# ENET.net
KiCad netlist of a schematic drawn in Altium Designer
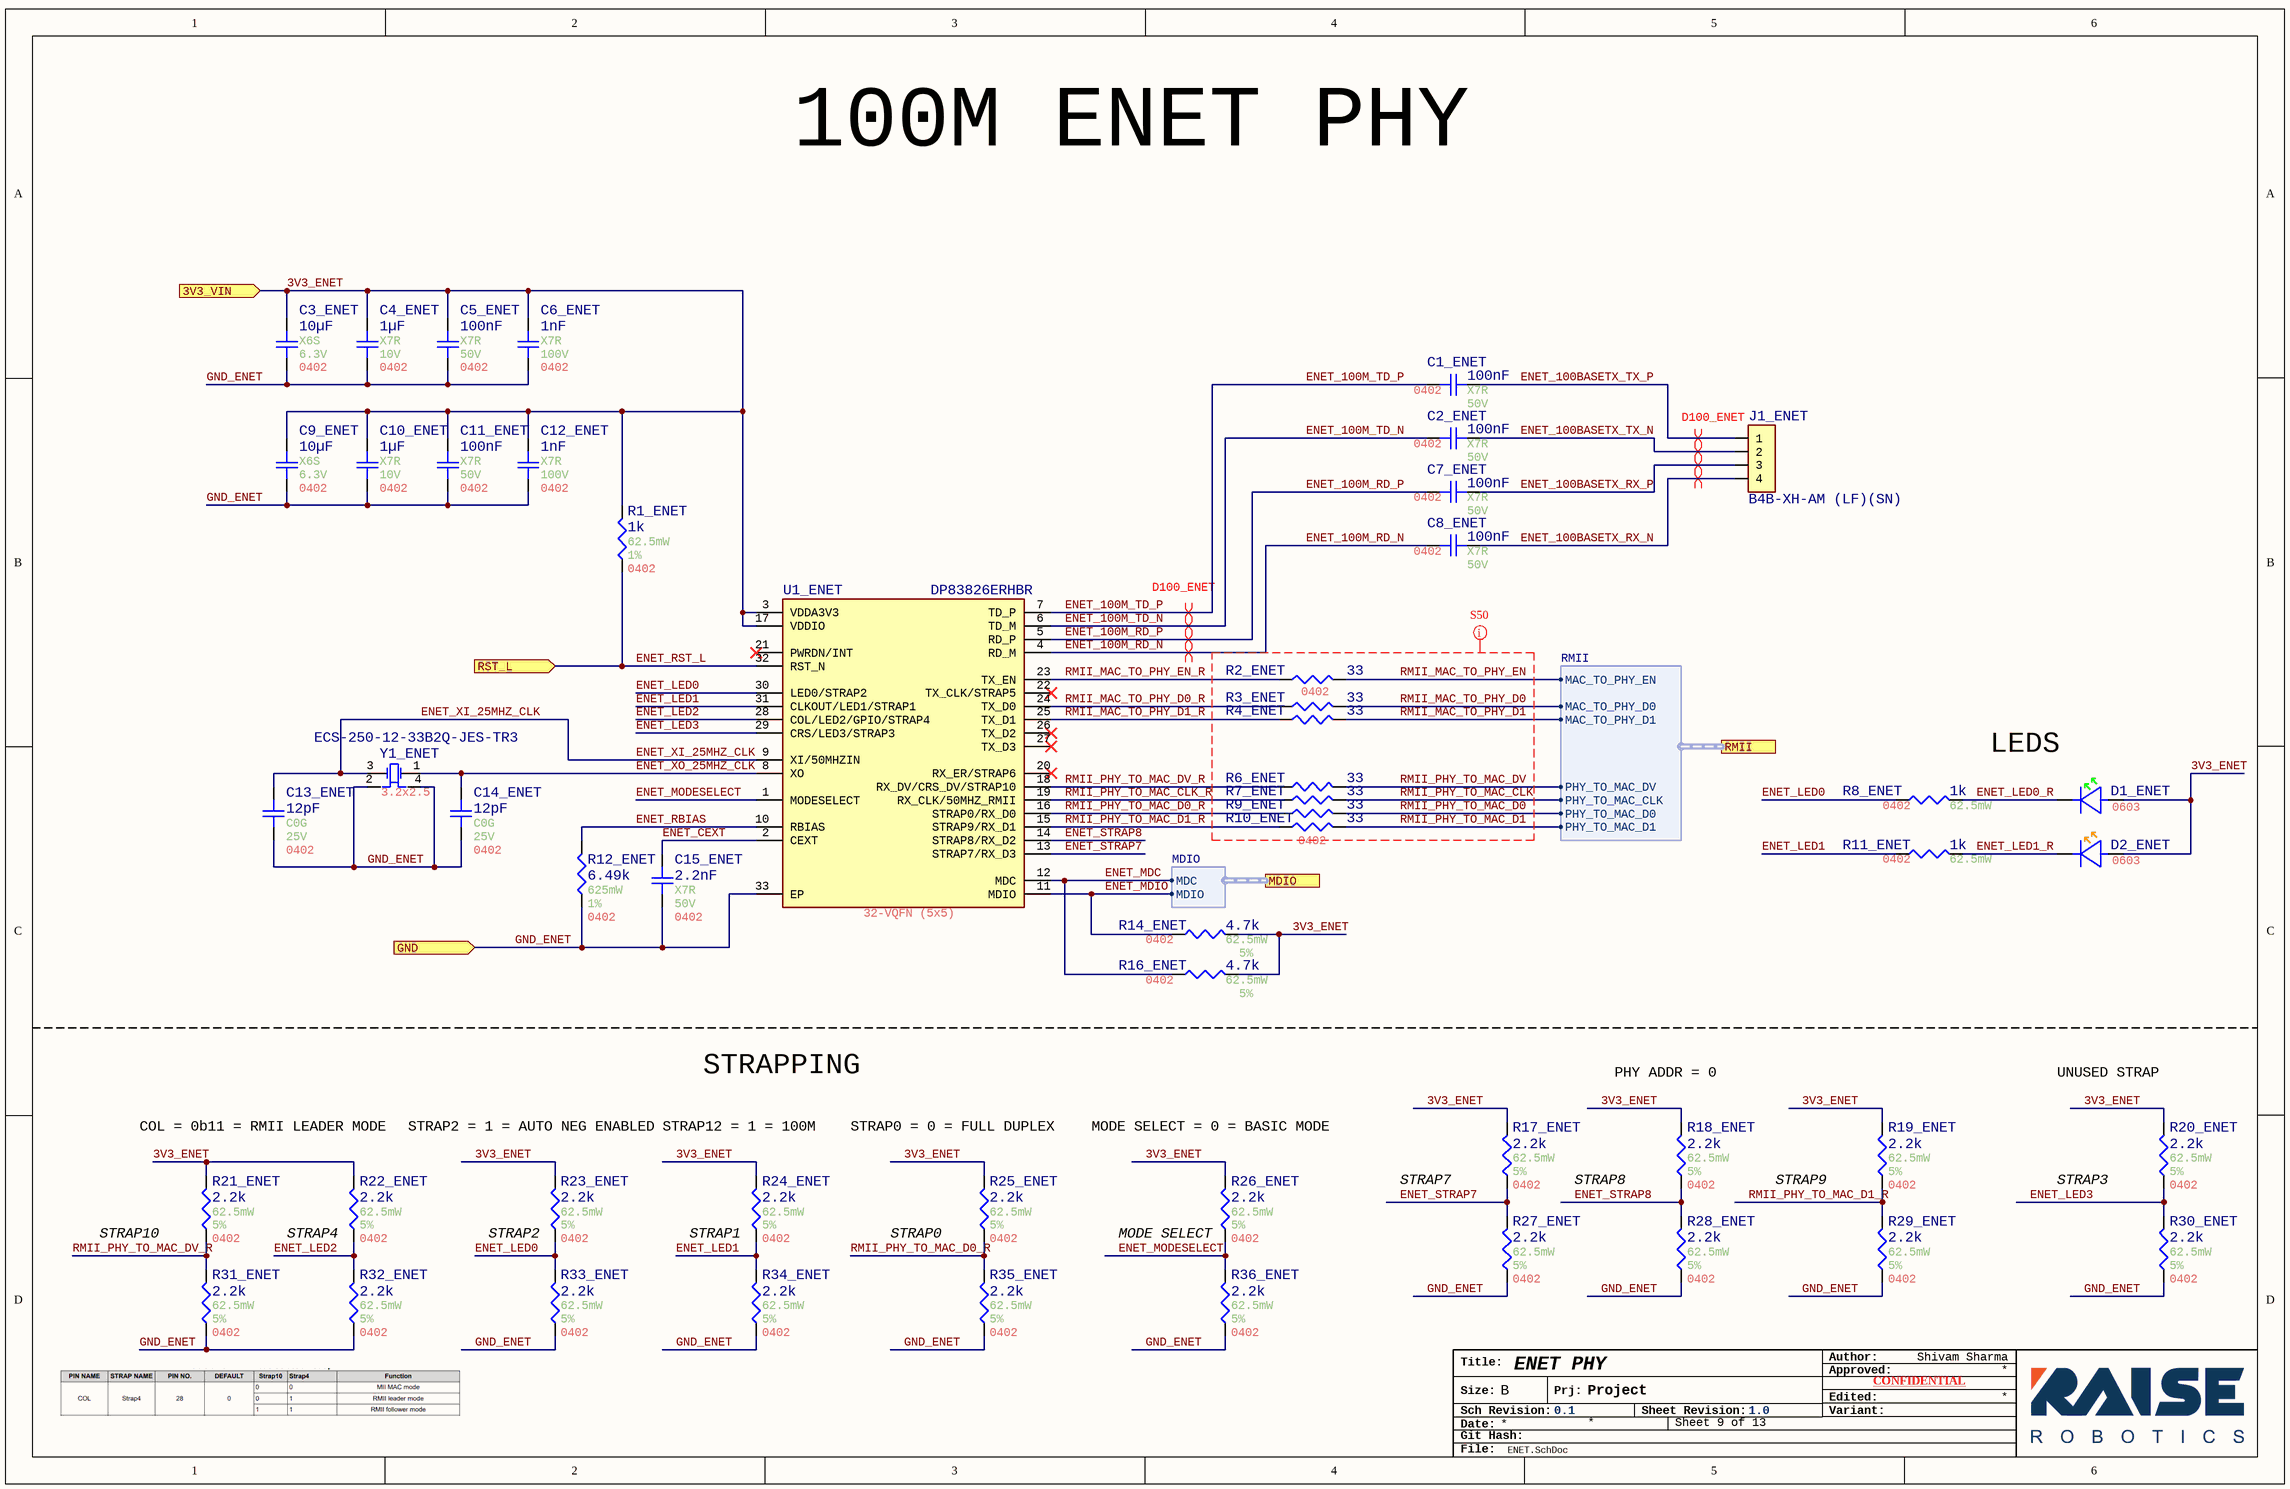
[diagram p0: ENET.SchDoc]

(export (version "E")
  (design (tool "Eeschema 10.0.6"))
  (components
    (comp (ref "C1_ENET")
      (value "100nF")
      (footprint "Generic 0402 capacitor")
      (fields
        (field (name "TEMPERATURE COEFFICIENT") "X7R")
        (field (name "VOLTAGE RATING") "50V")
        (field (name "CASE/PACKAGE") "0402")
        (field (name "TOLERANCE") "10%")
        (field (name "Comment") "GRT155R71H104KE01D")
      )
      (libsource (lib "Raise Robotics") (part "Unpolarized Capacitor"))
    )
    (comp (ref "C2_ENET")
      (value "100nF")
      (footprint "Generic 0402 capacitor")
      (fields
        (field (name "TEMPERATURE COEFFICIENT") "X7R")
        (field (name "VOLTAGE RATING") "50V")
        (field (name "CASE/PACKAGE") "0402")
        (field (name "TOLERANCE") "10%")
        (field (name "Comment") "GRT155R71H104KE01D")
      )
      (libsource (lib "Raise Robotics") (part "Unpolarized Capacitor"))
    )
    (comp (ref "C3_ENET")
      (value "10µF")
      (footprint "Generic 0402 capacitor")
      (description "Multilayer Ceramic Capacitors MLCC - SMD/SMT 0402 10uF 6.3VDC 20% X6S AEC-Q200")
      (fields
        (field (name "TEMPERATURE COEFFICIENT") "X6S")
        (field (name "VOLTAGE RATING") "6.3V")
        (field (name "CASE/PACKAGE") "0402")
        (field (name "TOLERANCE") "20%")
        (field (name "Comment") "GRT155C80J106ME13J")
      )
      (libsource (lib "Raise Robotics") (part "Unpolarized Capacitor"))
    )
    (comp (ref "C4_ENET")
      (value "1µF")
      (footprint "Generic 0402 capacitor")
      (description "Cap Cer 1UF 20V X7T 0402")
      (fields
        (field (name "TEMPERATURE COEFFICIENT") "X7R")
        (field (name "VOLTAGE RATING") "10V")
        (field (name "CASE/PACKAGE") "0402")
        (field (name "TOLERANCE") "20%")
        (field (name "Comment") "MAASL105CD7105MFCA01")
      )
      (libsource (lib "Raise Robotics") (part "Unpolarized Capacitor"))
    )
    (comp (ref "C5_ENET")
      (value "100nF")
      (footprint "Generic 0402 capacitor")
      (fields
        (field (name "TEMPERATURE COEFFICIENT") "X7R")
        (field (name "VOLTAGE RATING") "50V")
        (field (name "CASE/PACKAGE") "0402")
        (field (name "TOLERANCE") "10%")
        (field (name "Comment") "GRT155R71H104KE01D")
      )
      (libsource (lib "Raise Robotics") (part "Unpolarized Capacitor"))
    )
    (comp (ref "C6_ENET")
      (value "1nF")
      (footprint "Generic 0402 capacitor")
      (fields
        (field (name "TEMPERATURE COEFFICIENT") "X7R")
        (field (name "VOLTAGE RATING") "100V")
        (field (name "CASE/PACKAGE") "0402")
        (field (name "TOLERANCE") "10%")
        (field (name "Comment") "GCM155R72A102KA37J")
      )
      (libsource (lib "Raise Robotics") (part "Unpolarized Capacitor"))
    )
    (comp (ref "C7_ENET")
      (value "100nF")
      (footprint "Generic 0402 capacitor")
      (fields
        (field (name "TEMPERATURE COEFFICIENT") "X7R")
        (field (name "VOLTAGE RATING") "50V")
        (field (name "CASE/PACKAGE") "0402")
        (field (name "TOLERANCE") "10%")
        (field (name "Comment") "GRT155R71H104KE01D")
      )
      (libsource (lib "Raise Robotics") (part "Unpolarized Capacitor"))
    )
    (comp (ref "C8_ENET")
      (value "100nF")
      (footprint "Generic 0402 capacitor")
      (fields
        (field (name "TEMPERATURE COEFFICIENT") "X7R")
        (field (name "VOLTAGE RATING") "50V")
        (field (name "CASE/PACKAGE") "0402")
        (field (name "TOLERANCE") "10%")
        (field (name "Comment") "GRT155R71H104KE01D")
      )
      (libsource (lib "Raise Robotics") (part "Unpolarized Capacitor"))
    )
    (comp (ref "C9_ENET")
      (value "10µF")
      (footprint "Generic 0402 capacitor")
      (description "Multilayer Ceramic Capacitors MLCC - SMD/SMT 0402 10uF 6.3VDC 20% X6S AEC-Q200")
      (fields
        (field (name "TEMPERATURE COEFFICIENT") "X6S")
        (field (name "VOLTAGE RATING") "6.3V")
        (field (name "CASE/PACKAGE") "0402")
        (field (name "TOLERANCE") "20%")
        (field (name "Comment") "GRT155C80J106ME13J")
      )
      (libsource (lib "Raise Robotics") (part "Unpolarized Capacitor"))
    )
    (comp (ref "C10_ENET")
      (value "1µF")
      (footprint "Generic 0402 capacitor")
      (description "Cap Cer 1UF 20V X7T 0402")
      (fields
        (field (name "TEMPERATURE COEFFICIENT") "X7R")
        (field (name "VOLTAGE RATING") "10V")
        (field (name "CASE/PACKAGE") "0402")
        (field (name "TOLERANCE") "20%")
        (field (name "Comment") "MAASL105CD7105MFCA01")
      )
      (libsource (lib "Raise Robotics") (part "Unpolarized Capacitor"))
    )
    (comp (ref "C11_ENET")
      (value "100nF")
      (footprint "Generic 0402 capacitor")
      (fields
        (field (name "TEMPERATURE COEFFICIENT") "X7R")
        (field (name "VOLTAGE RATING") "50V")
        (field (name "CASE/PACKAGE") "0402")
        (field (name "TOLERANCE") "10%")
        (field (name "Comment") "GRT155R71H104KE01D")
      )
      (libsource (lib "Raise Robotics") (part "Unpolarized Capacitor"))
    )
    (comp (ref "C12_ENET")
      (value "1nF")
      (footprint "Generic 0402 capacitor")
      (fields
        (field (name "TEMPERATURE COEFFICIENT") "X7R")
        (field (name "VOLTAGE RATING") "100V")
        (field (name "CASE/PACKAGE") "0402")
        (field (name "TOLERANCE") "10%")
        (field (name "Comment") "GCM155R72A102KA37J")
      )
      (libsource (lib "Raise Robotics") (part "Unpolarized Capacitor"))
    )
    (comp (ref "C13_ENET")
      (value "12pF")
      (footprint "Generic 0402 capacitor")
      (fields
        (field (name "TEMPERATURE COEFFICIENT") "C0G")
        (field (name "VOLTAGE RATING") "25V")
        (field (name "CASE/PACKAGE") "0402")
        (field (name "TOLERANCE") "5%")
        (field (name "Comment") "GRT1555C1E120JA02J")
      )
      (libsource (lib "Raise Robotics") (part "Unpolarized Capacitor"))
    )
    (comp (ref "C14_ENET")
      (value "12pF")
      (footprint "Generic 0402 capacitor")
      (fields
        (field (name "TEMPERATURE COEFFICIENT") "C0G")
        (field (name "VOLTAGE RATING") "25V")
        (field (name "CASE/PACKAGE") "0402")
        (field (name "TOLERANCE") "5%")
        (field (name "Comment") "GRT1555C1E120JA02J")
      )
      (libsource (lib "Raise Robotics") (part "Unpolarized Capacitor"))
    )
    (comp (ref "C15_ENET")
      (value "2.2nF")
      (footprint "Generic 0402 capacitor")
      (description "50V 2.2nF X7R 卤10% 0402 Multilayer Ceramic Capacitors MLCC - SMD/SMT ROHS")
      (fields
        (field (name "TEMPERATURE COEFFICIENT") "X7R")
        (field (name "VOLTAGE RATING") "50V")
        (field (name "CASE/PACKAGE") "0402")
        (field (name "TOLERANCE") "10%")
        (field (name "Comment") "CGA2B2X7R1H222K050BA")
      )
      (libsource (lib "Raise Robotics") (part "Unpolarized Capacitor"))
    )
    (comp (ref "D1_ENET")
      (value "SML-D12P8WT86C")
      (footprint "SML-D12P8WT86C")
      (description "Green 560nm LED Indication - Discrete 2.2V 0603 (1608 Metric)")
      (fields (field (name "CASE/PACKAGE") "0603"))
      (libsource (lib "Raise Robotics") (part "LED Green"))
    )
    (comp (ref "D2_ENET")
      (value "SML-D12D8WT86C")
      (footprint "FP-SML-D12-MFG")
      (description "Orange 605nm LED Indication - Discrete 2.2V 0603 (1608 Metric)")
      (fields (field (name "CASE/PACKAGE") "0603"))
      (libsource (lib "Raise Robotics") (part "LED Orange"))
    )
    (comp (ref "J1_ENET")
      (value "B4B-XH-AM (LF)(SN)")
      (footprint "FP-B4B-XH-AM_LF_SN-MFG")
      (description "Header, Xh, Top, 4Way, 2.5Mm, Boss;")
      (fields (field (name "MANUFACTURER") "JST"))
      (libsource (lib "Raise Robotics") (part "4 pin generic conn"))
    )
    (comp (ref "R1_ENET")
      (value "1k")
      (footprint "Generic 0402 Resistor")
      (fields
        (field (name "POWER") "62.5mW")
        (field (name "TOLERANCE") "1%")
        (field (name "CASE/PACKAGE") "0402")
        (field (name "MANUFACTURER PART NUMBER") "Blank")
        (field (name "Comment") "WR04X1001FTL")
      )
      (libsource (lib "Raise Robotics") (part "Resistor"))
    )
    (comp (ref "R2_ENET")
      (value "33")
      (footprint "Generic 0402 Resistor")
      (fields
        (field (name "POWER") "625mW")
        (field (name "TOLERANCE") "1%")
        (field (name "Comment") "RMCA0402FT33R0-HP")
      )
      (libsource (lib "Raise Robotics") (part "Resistor"))
    )
    (comp (ref "R3_ENET")
      (value "33")
      (footprint "Generic 0402 Resistor")
      (fields
        (field (name "POWER") "625mW")
        (field (name "TOLERANCE") "1%")
        (field (name "Comment") "RMCA0402FT33R0-HP")
      )
      (libsource (lib "Raise Robotics") (part "Resistor"))
    )
    (comp (ref "R4_ENET")
      (value "33")
      (footprint "Generic 0402 Resistor")
      (fields
        (field (name "POWER") "625mW")
        (field (name "TOLERANCE") "1%")
        (field (name "CASE/PACKAGE") "0402")
        (field (name "Comment") "RMCA0402FT33R0-HP")
      )
      (libsource (lib "Raise Robotics") (part "Resistor"))
    )
    (comp (ref "R6_ENET")
      (value "33")
      (footprint "Generic 0402 Resistor")
      (fields
        (field (name "POWER") "625mW")
        (field (name "TOLERANCE") "1%")
        (field (name "Comment") "RMCA0402FT33R0-HP")
      )
      (libsource (lib "Raise Robotics") (part "Resistor"))
    )
    (comp (ref "R7_ENET")
      (value "33")
      (footprint "Generic 0402 Resistor")
      (fields
        (field (name "POWER") "625mW")
        (field (name "TOLERANCE") "1%")
        (field (name "Comment") "RMCA0402FT33R0-HP")
      )
      (libsource (lib "Raise Robotics") (part "Resistor"))
    )
    (comp (ref "R8_ENET")
      (value "1k")
      (footprint "Generic 0402 Resistor")
      (fields
        (field (name "POWER") "62.5mW")
        (field (name "TOLERANCE") "1%")
        (field (name "CASE/PACKAGE") "0402")
        (field (name "MANUFACTURER PART NUMBER") "Blank")
        (field (name "Comment") "WR04X1001FTL")
      )
      (libsource (lib "Raise Robotics") (part "Resistor"))
    )
    (comp (ref "R9_ENET")
      (value "33")
      (footprint "Generic 0402 Resistor")
      (fields
        (field (name "POWER") "625mW")
        (field (name "TOLERANCE") "1%")
        (field (name "Comment") "RMCA0402FT33R0-HP")
      )
      (libsource (lib "Raise Robotics") (part "Resistor"))
    )
    (comp (ref "R10_ENET")
      (value "33")
      (footprint "Generic 0402 Resistor")
      (fields
        (field (name "POWER") "625mW")
        (field (name "TOLERANCE") "1%")
        (field (name "CASE/PACKAGE") "0402")
        (field (name "Comment") "RMCA0402FT33R0-HP")
      )
      (libsource (lib "Raise Robotics") (part "Resistor"))
    )
    (comp (ref "R11_ENET")
      (value "1k")
      (footprint "Generic 0402 Resistor")
      (fields
        (field (name "POWER") "62.5mW")
        (field (name "TOLERANCE") "1%")
        (field (name "CASE/PACKAGE") "0402")
        (field (name "MANUFACTURER PART NUMBER") "Blank")
        (field (name "Comment") "WR04X1001FTL")
      )
      (libsource (lib "Raise Robotics") (part "Resistor"))
    )
    (comp (ref "R12_ENET")
      (value "6.49k")
      (footprint "Generic 0402 Resistor")
      (fields
        (field (name "POWER") "625mW")
        (field (name "TOLERANCE") "1%")
        (field (name "CASE/PACKAGE") "0402")
        (field (name "Comment") "AC0402FR-076K49L")
      )
      (libsource (lib "Raise Robotics") (part "Resistor"))
    )
    (comp (ref "R14_ENET")
      (value "4.7k")
      (footprint "Generic 0402 Resistor")
      (fields
        (field (name "POWER") "62.5mW")
        (field (name "TOLERANCE") "5%")
        (field (name "CASE/PACKAGE") "0402")
        (field (name "MANUFACTURER PART NUMBER") "Blank")
        (field (name "Comment") "WR04X472JTL")
      )
      (libsource (lib "Raise Robotics") (part "Resistor"))
    )
    (comp (ref "R16_ENET")
      (value "4.7k")
      (footprint "Generic 0402 Resistor")
      (fields
        (field (name "POWER") "62.5mW")
        (field (name "TOLERANCE") "5%")
        (field (name "CASE/PACKAGE") "0402")
        (field (name "MANUFACTURER PART NUMBER") "Blank")
        (field (name "Comment") "WR04X472JTL")
      )
      (libsource (lib "Raise Robotics") (part "Resistor"))
    )
    (comp (ref "R17_ENET")
      (value "2.2k")
      (footprint "Generic 0402 Resistor")
      (fields
        (field (name "POWER") "62.5mW")
        (field (name "TOLERANCE") "5%")
        (field (name "CASE/PACKAGE") "0402")
        (field (name "MANUFACTURER PART NUMBER") "Blank")
        (field (name "Comment") "CR0402-JW-222GLF")
      )
      (libsource (lib "Raise Robotics") (part "Resistor"))
    )
    (comp (ref "R18_ENET")
      (value "2.2k")
      (footprint "Generic 0402 Resistor")
      (fields
        (field (name "POWER") "62.5mW")
        (field (name "TOLERANCE") "5%")
        (field (name "CASE/PACKAGE") "0402")
        (field (name "MANUFACTURER PART NUMBER") "Blank")
        (field (name "Comment") "CR0402-JW-222GLF")
      )
      (libsource (lib "Raise Robotics") (part "Resistor"))
    )
    (comp (ref "R19_ENET")
      (value "2.2k")
      (footprint "Generic 0402 Resistor")
      (fields
        (field (name "POWER") "62.5mW")
        (field (name "TOLERANCE") "5%")
        (field (name "CASE/PACKAGE") "0402")
        (field (name "MANUFACTURER PART NUMBER") "Blank")
        (field (name "Comment") "CR0402-JW-222GLF")
      )
      (libsource (lib "Raise Robotics") (part "Resistor"))
    )
    (comp (ref "R20_ENET")
      (value "2.2k")
      (footprint "Generic 0402 Resistor")
      (fields
        (field (name "POWER") "62.5mW")
        (field (name "TOLERANCE") "5%")
        (field (name "CASE/PACKAGE") "0402")
        (field (name "MANUFACTURER PART NUMBER") "Blank")
        (field (name "Comment") "CR0402-JW-222GLF")
      )
      (libsource (lib "Raise Robotics") (part "Resistor"))
    )
    (comp (ref "R21_ENET")
      (value "2.2k")
      (footprint "Generic 0402 Resistor")
      (fields
        (field (name "POWER") "62.5mW")
        (field (name "TOLERANCE") "5%")
        (field (name "CASE/PACKAGE") "0402")
        (field (name "MANUFACTURER PART NUMBER") "Blank")
        (field (name "Comment") "CR0402-JW-222GLF")
      )
      (libsource (lib "Raise Robotics") (part "Resistor"))
    )
    (comp (ref "R22_ENET")
      (value "2.2k")
      (footprint "Generic 0402 Resistor")
      (fields
        (field (name "POWER") "62.5mW")
        (field (name "TOLERANCE") "5%")
        (field (name "CASE/PACKAGE") "0402")
        (field (name "MANUFACTURER PART NUMBER") "Blank")
        (field (name "Comment") "CR0402-JW-222GLF")
      )
      (libsource (lib "Raise Robotics") (part "Resistor"))
    )
    (comp (ref "R23_ENET")
      (value "2.2k")
      (footprint "Generic 0402 Resistor")
      (fields
        (field (name "POWER") "62.5mW")
        (field (name "TOLERANCE") "5%")
        (field (name "CASE/PACKAGE") "0402")
        (field (name "MANUFACTURER PART NUMBER") "Blank")
        (field (name "Comment") "CR0402-JW-222GLF")
      )
      (libsource (lib "Raise Robotics") (part "Resistor"))
    )
    (comp (ref "R24_ENET")
      (value "2.2k")
      (footprint "Generic 0402 Resistor")
      (fields
        (field (name "POWER") "62.5mW")
        (field (name "TOLERANCE") "5%")
        (field (name "CASE/PACKAGE") "0402")
        (field (name "MANUFACTURER PART NUMBER") "Blank")
        (field (name "Comment") "CR0402-JW-222GLF")
      )
      (libsource (lib "Raise Robotics") (part "Resistor"))
    )
    (comp (ref "R25_ENET")
      (value "2.2k")
      (footprint "Generic 0402 Resistor")
      (fields
        (field (name "POWER") "62.5mW")
        (field (name "TOLERANCE") "5%")
        (field (name "CASE/PACKAGE") "0402")
        (field (name "MANUFACTURER PART NUMBER") "Blank")
        (field (name "Comment") "CR0402-JW-222GLF")
      )
      (libsource (lib "Raise Robotics") (part "Resistor"))
    )
    (comp (ref "R26_ENET")
      (value "2.2k")
      (footprint "Generic 0402 Resistor")
      (fields
        (field (name "POWER") "62.5mW")
        (field (name "TOLERANCE") "5%")
        (field (name "CASE/PACKAGE") "0402")
        (field (name "MANUFACTURER PART NUMBER") "Blank")
        (field (name "Comment") "CR0402-JW-222GLF")
      )
      (libsource (lib "Raise Robotics") (part "Resistor"))
    )
    (comp (ref "R27_ENET")
      (value "2.2k")
      (footprint "Generic 0402 Resistor")
      (fields
        (field (name "POWER") "62.5mW")
        (field (name "TOLERANCE") "5%")
        (field (name "CASE/PACKAGE") "0402")
        (field (name "MANUFACTURER PART NUMBER") "Blank")
        (field (name "Comment") "CR0402-JW-222GLF")
      )
      (libsource (lib "Raise Robotics") (part "Resistor"))
    )
    (comp (ref "R28_ENET")
      (value "2.2k")
      (footprint "Generic 0402 Resistor")
      (fields
        (field (name "POWER") "62.5mW")
        (field (name "TOLERANCE") "5%")
        (field (name "CASE/PACKAGE") "0402")
        (field (name "MANUFACTURER PART NUMBER") "Blank")
        (field (name "Comment") "CR0402-JW-222GLF")
      )
      (libsource (lib "Raise Robotics") (part "Resistor"))
    )
    (comp (ref "R29_ENET")
      (value "2.2k")
      (footprint "Generic 0402 Resistor")
      (fields
        (field (name "POWER") "62.5mW")
        (field (name "TOLERANCE") "5%")
        (field (name "CASE/PACKAGE") "0402")
        (field (name "MANUFACTURER PART NUMBER") "Blank")
        (field (name "Comment") "CR0402-JW-222GLF")
      )
      (libsource (lib "Raise Robotics") (part "Resistor"))
    )
    (comp (ref "R30_ENET")
      (value "2.2k")
      (footprint "Generic 0402 Resistor")
      (fields
        (field (name "POWER") "62.5mW")
        (field (name "TOLERANCE") "5%")
        (field (name "CASE/PACKAGE") "0402")
        (field (name "MANUFACTURER PART NUMBER") "Blank")
        (field (name "Comment") "CR0402-JW-222GLF")
      )
      (libsource (lib "Raise Robotics") (part "Resistor"))
    )
    (comp (ref "R31_ENET")
      (value "2.2k")
      (footprint "Generic 0402 Resistor")
      (fields
        (field (name "POWER") "62.5mW")
        (field (name "TOLERANCE") "5%")
        (field (name "CASE/PACKAGE") "0402")
        (field (name "MANUFACTURER PART NUMBER") "Blank")
        (field (name "Comment") "CR0402-JW-222GLF")
      )
      (libsource (lib "Raise Robotics") (part "Resistor"))
    )
    (comp (ref "R32_ENET")
      (value "2.2k")
      (footprint "Generic 0402 Resistor")
      (fields
        (field (name "POWER") "62.5mW")
        (field (name "TOLERANCE") "5%")
        (field (name "CASE/PACKAGE") "0402")
        (field (name "MANUFACTURER PART NUMBER") "Blank")
        (field (name "Comment") "CR0402-JW-222GLF")
      )
      (libsource (lib "Raise Robotics") (part "Resistor"))
    )
    (comp (ref "R33_ENET")
      (value "2.2k")
      (footprint "Generic 0402 Resistor")
      (fields
        (field (name "POWER") "62.5mW")
        (field (name "TOLERANCE") "5%")
        (field (name "CASE/PACKAGE") "0402")
        (field (name "MANUFACTURER PART NUMBER") "Blank")
        (field (name "Comment") "CR0402-JW-222GLF")
      )
      (libsource (lib "Raise Robotics") (part "Resistor"))
    )
    (comp (ref "R34_ENET")
      (value "2.2k")
      (footprint "Generic 0402 Resistor")
      (fields
        (field (name "POWER") "62.5mW")
        (field (name "TOLERANCE") "5%")
        (field (name "CASE/PACKAGE") "0402")
        (field (name "MANUFACTURER PART NUMBER") "Blank")
        (field (name "Comment") "CR0402-JW-222GLF")
      )
      (libsource (lib "Raise Robotics") (part "Resistor"))
    )
    (comp (ref "R35_ENET")
      (value "2.2k")
      (footprint "Generic 0402 Resistor")
      (fields
        (field (name "POWER") "62.5mW")
        (field (name "TOLERANCE") "5%")
        (field (name "CASE/PACKAGE") "0402")
        (field (name "MANUFACTURER PART NUMBER") "Blank")
        (field (name "Comment") "CR0402-JW-222GLF")
      )
      (libsource (lib "Raise Robotics") (part "Resistor"))
    )
    (comp (ref "R36_ENET")
      (value "2.2k")
      (footprint "Generic 0402 Resistor")
      (fields
        (field (name "POWER") "62.5mW")
        (field (name "TOLERANCE") "5%")
        (field (name "CASE/PACKAGE") "0402")
        (field (name "MANUFACTURER PART NUMBER") "Blank")
        (field (name "Comment") "CR0402-JW-222GLF")
      )
      (libsource (lib "Raise Robotics") (part "Resistor"))
    )
    (comp (ref "U1_ENET")
      (value "DP83826ERHBR")
      (footprint "DP83826ERHBR")
      (description "Ethernet Transceiver, 1-Trnsvr, PQCC32")
      (fields (field (name "CASE/PACKAGE") "32-VQFN (5x5)"))
      (libsource (lib "Raise Robotics") (part "DP83826ERHBR"))
    )
    (comp (ref "Y1_ENET")
      (value "ECS-250-12-33B2Q-JES-TR3")
      (footprint "ECS-250-12-33B2Q-JES-TR3")
      (description "Crystal 25.000 Mhz 12PF SMD")
      (fields (field (name "CASE/PACKAGE") "3.2x2.5"))
      (libsource (lib "Raise Robotics") (part "XTAL-2"))
    )
  )
  (nets
    (net (code "3") (name "/3V3_ENET") (class "Default")
      (node (ref "C10_ENET") (pin "2") (pinfunction "2_2") (pintype "passive"))
      (node (ref "C11_ENET") (pin "2") (pinfunction "2_2") (pintype "passive"))
      (node (ref "C12_ENET") (pin "2") (pinfunction "2_2") (pintype "passive"))
      (node (ref "C3_ENET") (pin "2") (pinfunction "2_2") (pintype "passive"))
      (node (ref "C4_ENET") (pin "2") (pinfunction "2_2") (pintype "passive"))
      (node (ref "C5_ENET") (pin "2") (pinfunction "2_2") (pintype "passive"))
      (node (ref "C6_ENET") (pin "2") (pinfunction "2_2") (pintype "passive"))
      (node (ref "C9_ENET") (pin "2") (pinfunction "2_2") (pintype "passive"))
      (node (ref "D1_ENET") (pin "2") (pinfunction "A_2") (pintype "passive"))
      (node (ref "D2_ENET") (pin "2") (pinfunction "A_2") (pintype "passive"))
      (node (ref "R14_ENET") (pin "2") (pinfunction "2_2") (pintype "passive"))
      (node (ref "R16_ENET") (pin "2") (pinfunction "2_2") (pintype "passive"))
      (node (ref "R17_ENET") (pin "2") (pinfunction "2_2") (pintype "passive"))
      (node (ref "R18_ENET") (pin "2") (pinfunction "2_2") (pintype "passive"))
      (node (ref "R19_ENET") (pin "2") (pinfunction "2_2") (pintype "passive"))
      (node (ref "R1_ENET") (pin "2") (pinfunction "2_2") (pintype "passive"))
      (node (ref "R20_ENET") (pin "2") (pinfunction "2_2") (pintype "passive"))
      (node (ref "R21_ENET") (pin "2") (pinfunction "2_2") (pintype "passive"))
      (node (ref "R22_ENET") (pin "2") (pinfunction "2_2") (pintype "passive"))
      (node (ref "R23_ENET") (pin "2") (pinfunction "2_2") (pintype "passive"))
      (node (ref "R24_ENET") (pin "2") (pinfunction "2_2") (pintype "passive"))
      (node (ref "R25_ENET") (pin "2") (pinfunction "2_2") (pintype "passive"))
      (node (ref "R26_ENET") (pin "2") (pinfunction "2_2") (pintype "passive"))
      (node (ref "U1_ENET") (pin "17") (pinfunction "VDDIO_17") (pintype "passive"))
      (node (ref "U1_ENET") (pin "3") (pinfunction "VDDA3V3_3") (pintype "passive"))
    )
    (net (code "4") (name "/ENET_100BASETX_RX_N") (class "Default")
      (node (ref "C8_ENET") (pin "1") (pinfunction "1_1") (pintype "passive"))
      (node (ref "J1_ENET") (pin "4") (pinfunction "4_4") (pintype "passive"))
    )
    (net (code "5") (name "/ENET_100BASETX_RX_P") (class "Default")
      (node (ref "C7_ENET") (pin "1") (pinfunction "1_1") (pintype "passive"))
      (node (ref "J1_ENET") (pin "3") (pinfunction "3_3") (pintype "passive"))
    )
    (net (code "6") (name "/ENET_100BASETX_TX_N") (class "Default")
      (node (ref "C2_ENET") (pin "1") (pinfunction "1_1") (pintype "passive"))
      (node (ref "J1_ENET") (pin "2") (pinfunction "2_2") (pintype "passive"))
    )
    (net (code "7") (name "/ENET_100BASETX_TX_P") (class "Default")
      (node (ref "C1_ENET") (pin "1") (pinfunction "1_1") (pintype "passive"))
      (node (ref "J1_ENET") (pin "1") (pinfunction "1_1") (pintype "passive"))
    )
    (net (code "8") (name "/ENET_100M_RD_N") (class "Default")
      (node (ref "C8_ENET") (pin "2") (pinfunction "2_2") (pintype "passive"))
      (node (ref "U1_ENET") (pin "4") (pinfunction "RD_M_4") (pintype "passive"))
    )
    (net (code "9") (name "/ENET_100M_RD_P") (class "Default")
      (node (ref "C7_ENET") (pin "2") (pinfunction "2_2") (pintype "passive"))
      (node (ref "U1_ENET") (pin "5") (pinfunction "RD_P_5") (pintype "passive"))
    )
    (net (code "10") (name "/ENET_100M_TD_N") (class "Default")
      (node (ref "C2_ENET") (pin "2") (pinfunction "2_2") (pintype "passive"))
      (node (ref "U1_ENET") (pin "6") (pinfunction "TD_M_6") (pintype "passive"))
    )
    (net (code "11") (name "/ENET_100M_TD_P") (class "Default")
      (node (ref "C1_ENET") (pin "2") (pinfunction "2_2") (pintype "passive"))
      (node (ref "U1_ENET") (pin "7") (pinfunction "TD_P_7") (pintype "passive"))
    )
    (net (code "12") (name "/ENET_CEXT") (class "Default")
      (node (ref "C15_ENET") (pin "2") (pinfunction "2_2") (pintype "passive"))
      (node (ref "U1_ENET") (pin "2") (pinfunction "CEXT_2") (pintype "passive"))
    )
    (net (code "13") (name "/ENET_LED0") (class "Default")
      (node (ref "R23_ENET") (pin "1") (pinfunction "1_1") (pintype "passive"))
      (node (ref "R33_ENET") (pin "2") (pinfunction "2_2") (pintype "passive"))
      (node (ref "R8_ENET") (pin "1") (pinfunction "1_1") (pintype "passive"))
      (node (ref "U1_ENET") (pin "30") (pinfunction "LED0/STRAP2_30") (pintype "passive"))
    )
    (net (code "14") (name "/ENET_LED0_R") (class "Default")
      (node (ref "D1_ENET") (pin "1") (pinfunction "C_1") (pintype "passive"))
      (node (ref "R8_ENET") (pin "2") (pinfunction "2_2") (pintype "passive"))
    )
    (net (code "15") (name "/ENET_LED1") (class "Default")
      (node (ref "R11_ENET") (pin "1") (pinfunction "1_1") (pintype "passive"))
      (node (ref "R24_ENET") (pin "1") (pinfunction "1_1") (pintype "passive"))
      (node (ref "R34_ENET") (pin "2") (pinfunction "2_2") (pintype "passive"))
      (node (ref "U1_ENET") (pin "31") (pinfunction "CLKOUT/LED1/STRAP1_31") (pintype "passive"))
    )
    (net (code "16") (name "/ENET_LED1_R") (class "Default")
      (node (ref "D2_ENET") (pin "1") (pinfunction "C_1") (pintype "passive"))
      (node (ref "R11_ENET") (pin "2") (pinfunction "2_2") (pintype "passive"))
    )
    (net (code "17") (name "/ENET_LED2") (class "Default")
      (node (ref "R22_ENET") (pin "1") (pinfunction "1_1") (pintype "passive"))
      (node (ref "R32_ENET") (pin "2") (pinfunction "2_2") (pintype "passive"))
      (node (ref "U1_ENET") (pin "28") (pinfunction "COL/LED2/GPIO/STRAP4_28") (pintype "passive"))
    )
    (net (code "18") (name "/ENET_LED3") (class "Default")
      (node (ref "R20_ENET") (pin "1") (pinfunction "1_1") (pintype "passive"))
      (node (ref "R30_ENET") (pin "2") (pinfunction "2_2") (pintype "passive"))
      (node (ref "U1_ENET") (pin "29") (pinfunction "CRS/LED3/STRAP3_29") (pintype "passive"))
    )
    (net (code "19") (name "/ENET_MDC") (class "Default")
      (node (ref "R16_ENET") (pin "1") (pinfunction "1_1") (pintype "passive"))
      (node (ref "U1_ENET") (pin "12") (pinfunction "MDC_12") (pintype "passive"))
    )
    (net (code "20") (name "/ENET_MDIO") (class "Default")
      (node (ref "R14_ENET") (pin "1") (pinfunction "1_1") (pintype "passive"))
      (node (ref "U1_ENET") (pin "11") (pinfunction "MDIO_11") (pintype "passive"))
    )
    (net (code "21") (name "/ENET_MODESELECT") (class "Default")
      (node (ref "R26_ENET") (pin "1") (pinfunction "1_1") (pintype "passive"))
      (node (ref "R36_ENET") (pin "2") (pinfunction "2_2") (pintype "passive"))
      (node (ref "U1_ENET") (pin "1") (pinfunction "MODESELECT_1") (pintype "passive"))
    )
    (net (code "22") (name "/ENET_RBIAS") (class "Default")
      (node (ref "R12_ENET") (pin "2") (pinfunction "2_2") (pintype "passive"))
      (node (ref "U1_ENET") (pin "10") (pinfunction "RBIAS_10") (pintype "passive"))
    )
    (net (code "23") (name "/ENET_RST_L") (class "Default")
      (node (ref "R1_ENET") (pin "1") (pinfunction "1_1") (pintype "passive"))
      (node (ref "U1_ENET") (pin "32") (pinfunction "RST_N_32") (pintype "passive"))
    )
    (net (code "24") (name "/ENET_STRAP7") (class "Default")
      (node (ref "R17_ENET") (pin "1") (pinfunction "1_1") (pintype "passive"))
      (node (ref "R27_ENET") (pin "2") (pinfunction "2_2") (pintype "passive"))
      (node (ref "U1_ENET") (pin "13") (pinfunction "STRAP7/RX_D3_13") (pintype "passive"))
    )
    (net (code "25") (name "/ENET_STRAP8") (class "Default")
      (node (ref "R18_ENET") (pin "1") (pinfunction "1_1") (pintype "passive"))
      (node (ref "R28_ENET") (pin "2") (pinfunction "2_2") (pintype "passive"))
      (node (ref "U1_ENET") (pin "14") (pinfunction "STRAP8/RX_D2_14") (pintype "passive"))
    )
    (net (code "26") (name "/ENET_XI_25MHZ_CLK") (class "Default")
      (node (ref "C13_ENET") (pin "2") (pinfunction "2_2") (pintype "passive"))
      (node (ref "U1_ENET") (pin "9") (pinfunction "XI/50MHZIN_9") (pintype "passive"))
      (node (ref "Y1_ENET") (pin "3") (pinfunction "3_3") (pintype "passive"))
    )
    (net (code "27") (name "/ENET_XO_25MHZ_CLK") (class "Default")
      (node (ref "C14_ENET") (pin "2") (pinfunction "2_2") (pintype "passive"))
      (node (ref "U1_ENET") (pin "8") (pinfunction "XO_8") (pintype "passive"))
      (node (ref "Y1_ENET") (pin "1") (pinfunction "1_1") (pintype "passive"))
    )
    (net (code "28") (name "/GND_ENET") (class "Default")
      (node (ref "C10_ENET") (pin "1") (pinfunction "1_1") (pintype "passive"))
      (node (ref "C11_ENET") (pin "1") (pinfunction "1_1") (pintype "passive"))
      (node (ref "C12_ENET") (pin "1") (pinfunction "1_1") (pintype "passive"))
      (node (ref "C13_ENET") (pin "1") (pinfunction "1_1") (pintype "passive"))
      (node (ref "C14_ENET") (pin "1") (pinfunction "1_1") (pintype "passive"))
      (node (ref "C15_ENET") (pin "1") (pinfunction "1_1") (pintype "passive"))
      (node (ref "C3_ENET") (pin "1") (pinfunction "1_1") (pintype "passive"))
      (node (ref "C4_ENET") (pin "1") (pinfunction "1_1") (pintype "passive"))
      (node (ref "C5_ENET") (pin "1") (pinfunction "1_1") (pintype "passive"))
      (node (ref "C6_ENET") (pin "1") (pinfunction "1_1") (pintype "passive"))
      (node (ref "C9_ENET") (pin "1") (pinfunction "1_1") (pintype "passive"))
      (node (ref "R12_ENET") (pin "1") (pinfunction "1_1") (pintype "passive"))
      (node (ref "R27_ENET") (pin "1") (pinfunction "1_1") (pintype "passive"))
      (node (ref "R28_ENET") (pin "1") (pinfunction "1_1") (pintype "passive"))
      (node (ref "R29_ENET") (pin "1") (pinfunction "1_1") (pintype "passive"))
      (node (ref "R30_ENET") (pin "1") (pinfunction "1_1") (pintype "passive"))
      (node (ref "R31_ENET") (pin "1") (pinfunction "1_1") (pintype "passive"))
      (node (ref "R32_ENET") (pin "1") (pinfunction "1_1") (pintype "passive"))
      (node (ref "R33_ENET") (pin "1") (pinfunction "1_1") (pintype "passive"))
      (node (ref "R34_ENET") (pin "1") (pinfunction "1_1") (pintype "passive"))
      (node (ref "R35_ENET") (pin "1") (pinfunction "1_1") (pintype "passive"))
      (node (ref "R36_ENET") (pin "1") (pinfunction "1_1") (pintype "passive"))
      (node (ref "U1_ENET") (pin "33") (pinfunction "EP_33") (pintype "passive"))
      (node (ref "Y1_ENET") (pin "2") (pinfunction "2_2") (pintype "passive"))
      (node (ref "Y1_ENET") (pin "4") (pinfunction "4_4") (pintype "passive"))
    )
    (net (code "29") (name "/RMII_MAC_TO_PHY_D0") (class "Default")
      (node (ref "R3_ENET") (pin "2") (pinfunction "2_2") (pintype "passive"))
    )
    (net (code "30") (name "/RMII_MAC_TO_PHY_D0_R") (class "Default")
      (node (ref "R3_ENET") (pin "1") (pinfunction "1_1") (pintype "passive"))
      (node (ref "U1_ENET") (pin "24") (pinfunction "TX_D0_24") (pintype "passive"))
    )
    (net (code "31") (name "/RMII_MAC_TO_PHY_D1") (class "Default")
      (node (ref "R4_ENET") (pin "2") (pinfunction "2_2") (pintype "passive"))
    )
    (net (code "32") (name "/RMII_MAC_TO_PHY_D1_R") (class "Default")
      (node (ref "R4_ENET") (pin "1") (pinfunction "1_1") (pintype "passive"))
      (node (ref "U1_ENET") (pin "25") (pinfunction "TX_D1_25") (pintype "passive"))
    )
    (net (code "33") (name "/RMII_MAC_TO_PHY_EN") (class "Default")
      (node (ref "R2_ENET") (pin "2") (pinfunction "2_2") (pintype "passive"))
    )
    (net (code "34") (name "/RMII_MAC_TO_PHY_EN_R") (class "Default")
      (node (ref "R2_ENET") (pin "1") (pinfunction "1_1") (pintype "passive"))
      (node (ref "U1_ENET") (pin "23") (pinfunction "TX_EN_23") (pintype "passive"))
    )
    (net (code "35") (name "/RMII_PHY_TO_MAC_CLK") (class "Default")
      (node (ref "R7_ENET") (pin "2") (pinfunction "2_2") (pintype "passive"))
    )
    (net (code "36") (name "/RMII_PHY_TO_MAC_CLK_R") (class "Default")
      (node (ref "R7_ENET") (pin "1") (pinfunction "1_1") (pintype "passive"))
      (node (ref "U1_ENET") (pin "19") (pinfunction "RX_CLK/50MHZ_RMII_19") (pintype "passive"))
    )
    (net (code "37") (name "/RMII_PHY_TO_MAC_D0") (class "Default")
      (node (ref "R9_ENET") (pin "2") (pinfunction "2_2") (pintype "passive"))
    )
    (net (code "38") (name "/RMII_PHY_TO_MAC_D0_R") (class "Default")
      (node (ref "R25_ENET") (pin "1") (pinfunction "1_1") (pintype "passive"))
      (node (ref "R35_ENET") (pin "2") (pinfunction "2_2") (pintype "passive"))
      (node (ref "R9_ENET") (pin "1") (pinfunction "1_1") (pintype "passive"))
      (node (ref "U1_ENET") (pin "16") (pinfunction "STRAP0/RX_D0_16") (pintype "passive"))
    )
    (net (code "39") (name "/RMII_PHY_TO_MAC_D1") (class "Default")
      (node (ref "R10_ENET") (pin "2") (pinfunction "2_2") (pintype "passive"))
    )
    (net (code "40") (name "/RMII_PHY_TO_MAC_D1_R") (class "Default")
      (node (ref "R10_ENET") (pin "1") (pinfunction "1_1") (pintype "passive"))
      (node (ref "R19_ENET") (pin "1") (pinfunction "1_1") (pintype "passive"))
      (node (ref "R29_ENET") (pin "2") (pinfunction "2_2") (pintype "passive"))
      (node (ref "U1_ENET") (pin "15") (pinfunction "STRAP9/RX_D1_15") (pintype "passive"))
    )
    (net (code "41") (name "/RMII_PHY_TO_MAC_DV") (class "Default")
      (node (ref "R6_ENET") (pin "2") (pinfunction "2_2") (pintype "passive"))
    )
    (net (code "42") (name "/RMII_PHY_TO_MAC_DV_R") (class "Default")
      (node (ref "R21_ENET") (pin "1") (pinfunction "1_1") (pintype "passive"))
      (node (ref "R31_ENET") (pin "2") (pinfunction "2_2") (pintype "passive"))
      (node (ref "R6_ENET") (pin "1") (pinfunction "1_1") (pintype "passive"))
      (node (ref "U1_ENET") (pin "18") (pinfunction "RX_DV/CRS_DV/STRAP10_18") (pintype "passive"))
    )
    (net (code "45") (name "unconnected-(U1_ENET-PWRDN{slash}INT-Pad21)") (class "Default")
      (node (ref "U1_ENET") (pin "21") (pinfunction "PWRDN/INT_21") (pintype "passive+no_connect"))
    )
    (net (code "46") (name "unconnected-(U1_ENET-RX_ER{slash}STRAP6-Pad20)") (class "Default")
      (node (ref "U1_ENET") (pin "20") (pinfunction "RX_ER/STRAP6_20") (pintype "passive+no_connect"))
    )
    (net (code "47") (name "unconnected-(U1_ENET-TX_CLK{slash}STRAP5-Pad22)") (class "Default")
      (node (ref "U1_ENET") (pin "22") (pinfunction "TX_CLK/STRAP5_22") (pintype "passive+no_connect"))
    )
    (net (code "48") (name "unconnected-(U1_ENET-TX_D2-Pad26)") (class "Default")
      (node (ref "U1_ENET") (pin "26") (pinfunction "TX_D2_26") (pintype "passive+no_connect"))
    )
    (net (code "49") (name "unconnected-(U1_ENET-TX_D3-Pad27)") (class "Default")
      (node (ref "U1_ENET") (pin "27") (pinfunction "TX_D3_27") (pintype "passive+no_connect"))
    )
  )
)
